# esquema-eletrico-17103449.net
KiCad netlist of a schematic drawn in EAGLE
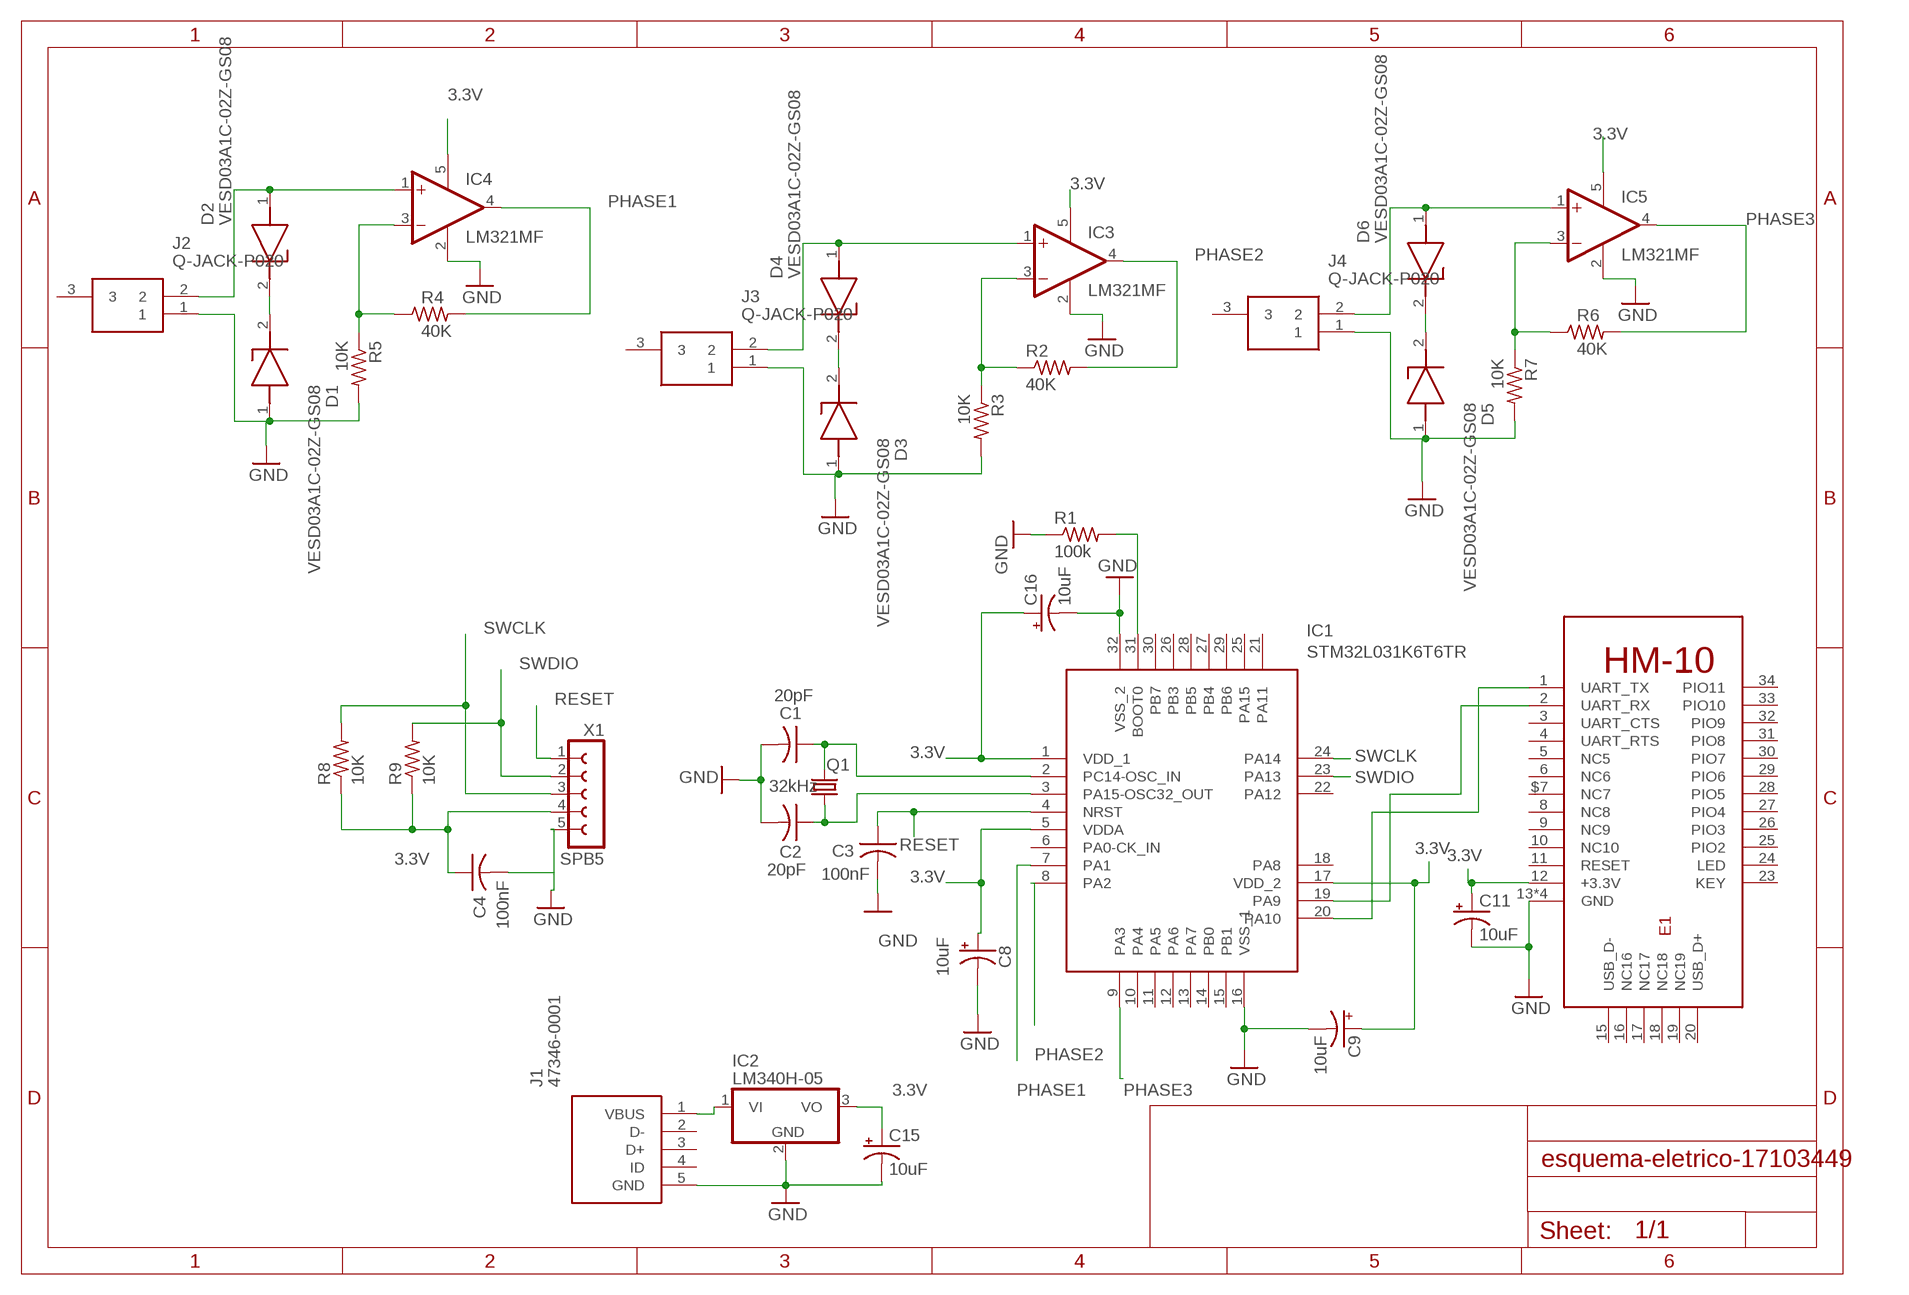
[diagram p0: schematic, sheet 1]

(export (version "E")
  (design (tool "Eeschema 10.0.6"))
  (components
    (comp (ref "C1")
      (value "20pF")
      (footprint "eagle-import:C0805")
      (libsource (lib "eagle-import") (part "C-USC0805"))
    )
    (comp (ref "C2")
      (value "20pF")
      (footprint "eagle-import:C0805")
      (libsource (lib "eagle-import") (part "C-USC0805"))
    )
    (comp (ref "C3")
      (value "100nF")
      (footprint "eagle-import:C0805")
      (libsource (lib "eagle-import") (part "C-USC0805"))
    )
    (comp (ref "C4")
      (value "100nF")
      (footprint "eagle-import:C0805")
      (libsource (lib "eagle-import") (part "C-USC0805"))
    )
    (comp (ref "C8")
      (value "10uF")
      (footprint "eagle-import:E2-5")
      (libsource (lib "eagle-import") (part "CPOL-USE2-5"))
    )
    (comp (ref "C9")
      (value "10uF")
      (footprint "eagle-import:E2-5")
      (libsource (lib "eagle-import") (part "CPOL-USE2-5"))
    )
    (comp (ref "C11")
      (value "10uF")
      (footprint "eagle-import:E2-5")
      (libsource (lib "eagle-import") (part "CPOL-USE2-5"))
    )
    (comp (ref "C15")
      (value "10uF")
      (footprint "eagle-import:E2-5")
      (libsource (lib "eagle-import") (part "CPOL-USE2-5"))
    )
    (comp (ref "C16")
      (value "10uF")
      (footprint "eagle-import:E2-5")
      (libsource (lib "eagle-import") (part "CPOL-USE2-5"))
    )
    (comp (ref "D1")
      (value "VESD03A1C-02Z-GS08")
      (footprint "eagle-import:VESD03A1C02ZGS08")
      (fields (field (name "MOUSER_PART_NUMBER") "78-VESD03A1C-02Z"))
      (libsource (lib "eagle-import") (part "VESD03A1C-02Z-GS08"))
    )
    (comp (ref "D2")
      (value "VESD03A1C-02Z-GS08")
      (footprint "eagle-import:VESD03A1C02ZGS08")
      (fields (field (name "MOUSER_PART_NUMBER") "78-VESD03A1C-02Z"))
      (libsource (lib "eagle-import") (part "VESD03A1C-02Z-GS08"))
    )
    (comp (ref "D3")
      (value "VESD03A1C-02Z-GS08")
      (footprint "eagle-import:VESD03A1C02ZGS08")
      (fields (field (name "MOUSER_PART_NUMBER") "78-VESD03A1C-02Z"))
      (libsource (lib "eagle-import") (part "VESD03A1C-02Z-GS08"))
    )
    (comp (ref "D4")
      (value "VESD03A1C-02Z-GS08")
      (footprint "eagle-import:VESD03A1C02ZGS08")
      (fields (field (name "MOUSER_PART_NUMBER") "78-VESD03A1C-02Z"))
      (libsource (lib "eagle-import") (part "VESD03A1C-02Z-GS08"))
    )
    (comp (ref "D5")
      (value "VESD03A1C-02Z-GS08")
      (footprint "eagle-import:VESD03A1C02ZGS08")
      (fields (field (name "MOUSER_PART_NUMBER") "78-VESD03A1C-02Z"))
      (libsource (lib "eagle-import") (part "VESD03A1C-02Z-GS08"))
    )
    (comp (ref "D6")
      (value "VESD03A1C-02Z-GS08")
      (footprint "eagle-import:VESD03A1C02ZGS08")
      (fields (field (name "MOUSER_PART_NUMBER") "78-VESD03A1C-02Z"))
      (libsource (lib "eagle-import") (part "VESD03A1C-02Z-GS08"))
    )
    (comp (ref "E1")
      (value "HM-10-BOARD")
      (footprint "eagle-import:26.9X13X2.2_BOARD")
      (libsource (lib "eagle-import") (part "HM-10-BOARD"))
    )
    (comp (ref "IC1")
      (value "STM32L031K6T6TR")
      (footprint "eagle-import:QFP80P900X900X160-32N")
      (fields (field (name "MOUSER_PART_NUMBER") "511-STM32L031K6T6TR"))
      (libsource (lib "eagle-import") (part "STM32L031K6T6TR"))
    )
    (comp (ref "IC2")
      (value "LM340H-05")
      (footprint "eagle-import:TO220H")
      (libsource (lib "eagle-import") (part "LM340?-H05"))
    )
    (comp (ref "IC3")
      (value "LM321MF")
      (footprint "eagle-import:SOT23-5")
      (libsource (lib "eagle-import") (part "LM321?MF"))
    )
    (comp (ref "IC4")
      (value "LM321MF")
      (footprint "eagle-import:SOT23-5")
      (libsource (lib "eagle-import") (part "LM321?MF"))
    )
    (comp (ref "IC5")
      (value "LM321MF")
      (footprint "eagle-import:SOT23-5")
      (libsource (lib "eagle-import") (part "LM321?MF"))
    )
    (comp (ref "J1")
      (value "47346-0001")
      (footprint "eagle-import:47346-0001")
      (fields (field (name "MOUSER_PART_NUMBER") "538-47346-0001"))
      (libsource (lib "eagle-import") (part "47346-0001"))
    )
    (comp (ref "J2")
      (value "Q-JACK-P020")
      (footprint "eagle-import:QJACKP020")
      (libsource (lib "eagle-import") (part "Q-JACK-P020"))
    )
    (comp (ref "J3")
      (value "Q-JACK-P020")
      (footprint "eagle-import:QJACKP020")
      (libsource (lib "eagle-import") (part "Q-JACK-P020"))
    )
    (comp (ref "J4")
      (value "Q-JACK-P020")
      (footprint "eagle-import:QJACKP020")
      (libsource (lib "eagle-import") (part "Q-JACK-P020"))
    )
    (comp (ref "Q1")
      (value "32kHz")
      (footprint "eagle-import:HC49_S")
      (libsource (lib "eagle-import") (part "CRYSTALHC49S"))
    )
    (comp (ref "R1")
      (value "100k")
      (footprint "eagle-import:0204_7")
      (libsource (lib "eagle-import") (part "R-US_0204/7"))
    )
    (comp (ref "R2")
      (value "40K")
      (footprint "eagle-import:WSC2515")
      (libsource (lib "eagle-import") (part "R-US_WSC2515"))
    )
    (comp (ref "R3")
      (value "10K")
      (footprint "eagle-import:WSC2515")
      (libsource (lib "eagle-import") (part "R-US_WSC2515"))
    )
    (comp (ref "R4")
      (value "40K")
      (footprint "eagle-import:WSC2515")
      (libsource (lib "eagle-import") (part "R-US_WSC2515"))
    )
    (comp (ref "R5")
      (value "10K")
      (footprint "eagle-import:WSC2515")
      (libsource (lib "eagle-import") (part "R-US_WSC2515"))
    )
    (comp (ref "R6")
      (value "40K")
      (footprint "eagle-import:WSC2515")
      (libsource (lib "eagle-import") (part "R-US_WSC2515"))
    )
    (comp (ref "R7")
      (value "10K")
      (footprint "eagle-import:WSC2515")
      (libsource (lib "eagle-import") (part "R-US_WSC2515"))
    )
    (comp (ref "R8")
      (value "10K")
      (footprint "eagle-import:WSC2515")
      (libsource (lib "eagle-import") (part "R-US_WSC2515"))
    )
    (comp (ref "R9")
      (value "10K")
      (footprint "eagle-import:WSC2515")
      (libsource (lib "eagle-import") (part "R-US_WSC2515"))
    )
    (comp (ref "X1")
      (value "SPB5")
      (footprint "eagle-import:SPB5")
      (libsource (lib "eagle-import") (part "SPB5"))
    )
  )
  (nets
    (net (code "1") (name "/3.3V") (class "Default")
      (node (ref "C11") (pin "+") (pinfunction "+_+") (pintype "passive"))
      (node (ref "C15") (pin "+") (pinfunction "+_+") (pintype "passive"))
      (node (ref "C16") (pin "+") (pinfunction "+_+") (pintype "passive"))
      (node (ref "C4") (pin "1") (pinfunction "1_1") (pintype "passive"))
      (node (ref "C8") (pin "+") (pinfunction "+_+") (pintype "passive"))
      (node (ref "C9") (pin "+") (pinfunction "+_+") (pintype "passive"))
      (node (ref "E1") (pin "12") (pinfunction "+3.3V_12") (pintype "bidirectional"))
      (node (ref "IC1") (pin "1") (pinfunction "VDD_1_1") (pintype "bidirectional"))
      (node (ref "IC1") (pin "17") (pinfunction "VDD_2_17") (pintype "bidirectional"))
      (node (ref "IC1") (pin "5") (pinfunction "VDDA_5") (pintype "bidirectional"))
      (node (ref "IC2") (pin "3") (pinfunction "VO_3") (pintype "passive"))
      (node (ref "IC3") (pin "5") (pinfunction "V+_5") (pintype "power_in"))
      (node (ref "IC4") (pin "5") (pinfunction "V+_5") (pintype "power_in"))
      (node (ref "R8") (pin "1") (pinfunction "1_1") (pintype "passive"))
      (node (ref "R9") (pin "1") (pinfunction "1_1") (pintype "passive"))
      (node (ref "X1") (pin "4") (pinfunction "4_4") (pintype "passive"))
    )
    (net (code "2") (name "/PHASE1") (class "Default")
      (node (ref "IC1") (pin "7") (pinfunction "PA1_7") (pintype "bidirectional"))
      (node (ref "IC4") (pin "4") (pinfunction "OUT_4") (pintype "output"))
      (node (ref "R4") (pin "2") (pinfunction "2_2") (pintype "passive"))
    )
    (net (code "3") (name "/PHASE2") (class "Default")
      (node (ref "IC1") (pin "8") (pinfunction "PA2_8") (pintype "bidirectional"))
      (node (ref "IC3") (pin "4") (pinfunction "OUT_4") (pintype "output"))
      (node (ref "R2") (pin "2") (pinfunction "2_2") (pintype "passive"))
    )
    (net (code "4") (name "/PHASE3") (class "Default")
      (node (ref "IC1") (pin "9") (pinfunction "PA3_9") (pintype "bidirectional"))
      (node (ref "IC5") (pin "4") (pinfunction "OUT_4") (pintype "output"))
      (node (ref "R6") (pin "2") (pinfunction "2_2") (pintype "passive"))
    )
    (net (code "5") (name "/RESET") (class "Default")
      (node (ref "C3") (pin "1") (pinfunction "1_1") (pintype "passive"))
      (node (ref "IC1") (pin "4") (pinfunction "NRST_4") (pintype "bidirectional"))
      (node (ref "X1") (pin "1") (pinfunction "1_1") (pintype "passive"))
    )
    (net (code "6") (name "/SWCLK") (class "Default")
      (node (ref "IC1") (pin "24") (pinfunction "PA14_24") (pintype "bidirectional"))
      (node (ref "R8") (pin "2") (pinfunction "2_2") (pintype "passive"))
      (node (ref "X1") (pin "3") (pinfunction "3_3") (pintype "passive"))
    )
    (net (code "7") (name "/SWDIO") (class "Default")
      (node (ref "IC1") (pin "23") (pinfunction "PA13_23") (pintype "bidirectional"))
      (node (ref "R9") (pin "2") (pinfunction "2_2") (pintype "passive"))
      (node (ref "X1") (pin "2") (pinfunction "2_2") (pintype "passive"))
    )
    (net (code "8") (name "GND") (class "Default")
      (node (ref "C1") (pin "2") (pinfunction "2_2") (pintype "passive"))
      (node (ref "C11") (pin "-") (pinfunction "-_-") (pintype "passive"))
      (node (ref "C15") (pin "-") (pinfunction "-_-") (pintype "passive"))
      (node (ref "C16") (pin "-") (pinfunction "-_-") (pintype "passive"))
      (node (ref "C2") (pin "2") (pinfunction "2_2") (pintype "passive"))
      (node (ref "C3") (pin "2") (pinfunction "2_2") (pintype "passive"))
      (node (ref "C4") (pin "2") (pinfunction "2_2") (pintype "passive"))
      (node (ref "C8") (pin "-") (pinfunction "-_-") (pintype "passive"))
      (node (ref "C9") (pin "-") (pinfunction "-_-") (pintype "passive"))
      (node (ref "D1") (pin "1") (pinfunction "A_1") (pintype "bidirectional"))
      (node (ref "D3") (pin "1") (pinfunction "A_1") (pintype "bidirectional"))
      (node (ref "D5") (pin "1") (pinfunction "A_1") (pintype "bidirectional"))
      (node (ref "E1") (pin "13") (pinfunction "GND_13") (pintype "bidirectional"))
      (node (ref "E1") (pin "14") (pinfunction "GND_14") (pintype "bidirectional"))
      (node (ref "E1") (pin "21") (pinfunction "GND_21") (pintype "bidirectional"))
      (node (ref "E1") (pin "22") (pinfunction "GND_22") (pintype "bidirectional"))
      (node (ref "IC1") (pin "16") (pinfunction "VSS_1_16") (pintype "bidirectional"))
      (node (ref "IC1") (pin "32") (pinfunction "VSS_2_32") (pintype "bidirectional"))
      (node (ref "IC2") (pin "2") (pinfunction "GND_2") (pintype "passive"))
      (node (ref "IC3") (pin "2") (pinfunction "V-_2") (pintype "power_in"))
      (node (ref "IC4") (pin "2") (pinfunction "V-_2") (pintype "power_in"))
      (node (ref "IC5") (pin "2") (pinfunction "V-_2") (pintype "power_in"))
      (node (ref "J1") (pin "5") (pinfunction "GND_5") (pintype "bidirectional"))
      (node (ref "J2") (pin "1") (pinfunction "1_1") (pintype "bidirectional"))
      (node (ref "J3") (pin "1") (pinfunction "1_1") (pintype "bidirectional"))
      (node (ref "J4") (pin "1") (pinfunction "1_1") (pintype "bidirectional"))
      (node (ref "R1") (pin "1") (pinfunction "1_1") (pintype "passive"))
      (node (ref "R3") (pin "2") (pinfunction "2_2") (pintype "passive"))
      (node (ref "R5") (pin "2") (pinfunction "2_2") (pintype "passive"))
      (node (ref "R7") (pin "2") (pinfunction "2_2") (pintype "passive"))
      (node (ref "X1") (pin "5") (pinfunction "5_5") (pintype "passive"))
    )
    (net (code "9") (name "Net-(D1-K)") (class "Default")
      (node (ref "D1") (pin "2") (pinfunction "K_2") (pintype "bidirectional"))
      (node (ref "D2") (pin "2") (pinfunction "K_2") (pintype "bidirectional"))
    )
    (net (code "10") (name "Net-(D2-A)") (class "Default")
      (node (ref "D2") (pin "1") (pinfunction "A_1") (pintype "bidirectional"))
      (node (ref "IC4") (pin "1") (pinfunction "+IN_1") (pintype "input"))
      (node (ref "J2") (pin "2") (pinfunction "2_2") (pintype "bidirectional"))
    )
    (net (code "11") (name "Net-(D3-K)") (class "Default")
      (node (ref "D3") (pin "2") (pinfunction "K_2") (pintype "bidirectional"))
      (node (ref "D4") (pin "2") (pinfunction "K_2") (pintype "bidirectional"))
    )
    (net (code "12") (name "Net-(D4-A)") (class "Default")
      (node (ref "D4") (pin "1") (pinfunction "A_1") (pintype "bidirectional"))
      (node (ref "IC3") (pin "1") (pinfunction "+IN_1") (pintype "input"))
      (node (ref "J3") (pin "2") (pinfunction "2_2") (pintype "bidirectional"))
    )
    (net (code "13") (name "Net-(D5-K)") (class "Default")
      (node (ref "D5") (pin "2") (pinfunction "K_2") (pintype "bidirectional"))
      (node (ref "D6") (pin "2") (pinfunction "K_2") (pintype "bidirectional"))
    )
    (net (code "14") (name "Net-(D6-A)") (class "Default")
      (node (ref "D6") (pin "1") (pinfunction "A_1") (pintype "bidirectional"))
      (node (ref "IC5") (pin "1") (pinfunction "+IN_1") (pintype "input"))
      (node (ref "J4") (pin "2") (pinfunction "2_2") (pintype "bidirectional"))
    )
    (net (code "15") (name "Net-(E1-UART_RX)") (class "Default")
      (node (ref "E1") (pin "2") (pinfunction "UART_RX_2") (pintype "bidirectional"))
      (node (ref "IC1") (pin "19") (pinfunction "PA9_19") (pintype "bidirectional"))
    )
    (net (code "16") (name "Net-(E1-UART_TX)") (class "Default")
      (node (ref "E1") (pin "1") (pinfunction "UART_TX_1") (pintype "bidirectional"))
      (node (ref "IC1") (pin "20") (pinfunction "PA10_20") (pintype "bidirectional"))
    )
    (net (code "17") (name "Net-(IC1-BOOT0)") (class "Default")
      (node (ref "IC1") (pin "31") (pinfunction "BOOT0_31") (pintype "bidirectional"))
      (node (ref "R1") (pin "2") (pinfunction "2_2") (pintype "passive"))
    )
    (net (code "18") (name "Net-(IC1-PA15-OSC32_OUT)") (class "Default")
      (node (ref "C2") (pin "1") (pinfunction "1_1") (pintype "passive"))
      (node (ref "IC1") (pin "3") (pinfunction "PA15-OSC32_OUT_3") (pintype "bidirectional"))
      (node (ref "Q1") (pin "1") (pinfunction "1_1") (pintype "passive"))
    )
    (net (code "19") (name "Net-(IC1-PC14-OSC_IN)") (class "Default")
      (node (ref "C1") (pin "1") (pinfunction "1_1") (pintype "passive"))
      (node (ref "IC1") (pin "2") (pinfunction "PC14-OSC_IN_2") (pintype "bidirectional"))
      (node (ref "Q1") (pin "2") (pinfunction "2_2") (pintype "passive"))
    )
    (net (code "20") (name "Net-(IC2-VI)") (class "Default")
      (node (ref "IC2") (pin "1") (pinfunction "VI_1") (pintype "input"))
      (node (ref "J1") (pin "1") (pinfunction "VBUS_1") (pintype "bidirectional"))
    )
    (net (code "21") (name "Net-(IC3--IN)") (class "Default")
      (node (ref "IC3") (pin "3") (pinfunction "-IN_3") (pintype "input"))
      (node (ref "R2") (pin "1") (pinfunction "1_1") (pintype "passive"))
      (node (ref "R3") (pin "1") (pinfunction "1_1") (pintype "passive"))
    )
    (net (code "22") (name "Net-(IC4--IN)") (class "Default")
      (node (ref "IC4") (pin "3") (pinfunction "-IN_3") (pintype "input"))
      (node (ref "R4") (pin "1") (pinfunction "1_1") (pintype "passive"))
      (node (ref "R5") (pin "1") (pinfunction "1_1") (pintype "passive"))
    )
    (net (code "23") (name "Net-(IC5--IN)") (class "Default")
      (node (ref "IC5") (pin "3") (pinfunction "-IN_3") (pintype "input"))
      (node (ref "R6") (pin "1") (pinfunction "1_1") (pintype "passive"))
      (node (ref "R7") (pin "1") (pinfunction "1_1") (pintype "passive"))
    )
    (net (code "24") (name "unconnected-(E1-KEY-Pad23)") (class "Default")
      (node (ref "E1") (pin "23") (pinfunction "KEY_23") (pintype "bidirectional"))
    )
    (net (code "25") (name "unconnected-(E1-LED-Pad24)") (class "Default")
      (node (ref "E1") (pin "24") (pinfunction "LED_24") (pintype "bidirectional"))
    )
    (net (code "26") (name "unconnected-(E1-NC5-Pad5)") (class "Default")
      (node (ref "E1") (pin "5") (pinfunction "NC5_5") (pintype "bidirectional"))
    )
    (net (code "27") (name "unconnected-(E1-NC6-Pad6)") (class "Default")
      (node (ref "E1") (pin "6") (pinfunction "NC6_6") (pintype "bidirectional"))
    )
    (net (code "28") (name "unconnected-(E1-NC7-Pad$7)") (class "Default")
      (node (ref "E1") (pin "$7") (pinfunction "NC7_$7") (pintype "bidirectional"))
    )
    (net (code "29") (name "unconnected-(E1-NC8-Pad8)") (class "Default")
      (node (ref "E1") (pin "8") (pinfunction "NC8_8") (pintype "bidirectional"))
    )
    (net (code "30") (name "unconnected-(E1-NC9-Pad9)") (class "Default")
      (node (ref "E1") (pin "9") (pinfunction "NC9_9") (pintype "bidirectional"))
    )
    (net (code "31") (name "unconnected-(E1-NC10-Pad10)") (class "Default")
      (node (ref "E1") (pin "10") (pinfunction "NC10_10") (pintype "bidirectional"))
    )
    (net (code "32") (name "unconnected-(E1-NC16-Pad16)") (class "Default")
      (node (ref "E1") (pin "16") (pinfunction "NC16_16") (pintype "bidirectional"))
    )
    (net (code "33") (name "unconnected-(E1-NC17-Pad17)") (class "Default")
      (node (ref "E1") (pin "17") (pinfunction "NC17_17") (pintype "bidirectional"))
    )
    (net (code "34") (name "unconnected-(E1-NC18-Pad18)") (class "Default")
      (node (ref "E1") (pin "18") (pinfunction "NC18_18") (pintype "bidirectional"))
    )
    (net (code "35") (name "unconnected-(E1-NC19-Pad19)") (class "Default")
      (node (ref "E1") (pin "19") (pinfunction "NC19_19") (pintype "bidirectional"))
    )
    (net (code "36") (name "unconnected-(E1-PIO2-Pad25)") (class "Default")
      (node (ref "E1") (pin "25") (pinfunction "PIO2_25") (pintype "bidirectional"))
    )
    (net (code "37") (name "unconnected-(E1-PIO3-Pad26)") (class "Default")
      (node (ref "E1") (pin "26") (pinfunction "PIO3_26") (pintype "bidirectional"))
    )
    (net (code "38") (name "unconnected-(E1-PIO4-Pad27)") (class "Default")
      (node (ref "E1") (pin "27") (pinfunction "PIO4_27") (pintype "bidirectional"))
    )
    (net (code "39") (name "unconnected-(E1-PIO5-Pad28)") (class "Default")
      (node (ref "E1") (pin "28") (pinfunction "PIO5_28") (pintype "bidirectional"))
    )
    (net (code "40") (name "unconnected-(E1-PIO6-Pad29)") (class "Default")
      (node (ref "E1") (pin "29") (pinfunction "PIO6_29") (pintype "bidirectional"))
    )
    (net (code "41") (name "unconnected-(E1-PIO7-Pad30)") (class "Default")
      (node (ref "E1") (pin "30") (pinfunction "PIO7_30") (pintype "bidirectional"))
    )
    (net (code "42") (name "unconnected-(E1-PIO8-Pad31)") (class "Default")
      (node (ref "E1") (pin "31") (pinfunction "PIO8_31") (pintype "bidirectional"))
    )
    (net (code "43") (name "unconnected-(E1-PIO9-Pad32)") (class "Default")
      (node (ref "E1") (pin "32") (pinfunction "PIO9_32") (pintype "bidirectional"))
    )
    (net (code "44") (name "unconnected-(E1-PIO10-Pad33)") (class "Default")
      (node (ref "E1") (pin "33") (pinfunction "PIO10_33") (pintype "bidirectional"))
    )
    (net (code "45") (name "unconnected-(E1-PIO11-Pad34)") (class "Default")
      (node (ref "E1") (pin "34") (pinfunction "PIO11_34") (pintype "bidirectional"))
    )
    (net (code "46") (name "unconnected-(E1-RESET-Pad11)") (class "Default")
      (node (ref "E1") (pin "11") (pinfunction "RESET_11") (pintype "bidirectional"))
    )
    (net (code "47") (name "unconnected-(E1-UART_CTS-Pad3)") (class "Default")
      (node (ref "E1") (pin "3") (pinfunction "UART_CTS_3") (pintype "bidirectional"))
    )
    (net (code "48") (name "unconnected-(E1-UART_RTS-Pad4)") (class "Default")
      (node (ref "E1") (pin "4") (pinfunction "UART_RTS_4") (pintype "bidirectional"))
    )
    (net (code "49") (name "unconnected-(E1-USB_D+-Pad20)") (class "Default")
      (node (ref "E1") (pin "20") (pinfunction "USB_D+_20") (pintype "bidirectional"))
    )
    (net (code "50") (name "unconnected-(E1-USB_D--Pad15)") (class "Default")
      (node (ref "E1") (pin "15") (pinfunction "USB_D-_15") (pintype "bidirectional"))
    )
    (net (code "51") (name "unconnected-(IC1-PA0-CK_IN-Pad6)") (class "Default")
      (node (ref "IC1") (pin "6") (pinfunction "PA0-CK_IN_6") (pintype "bidirectional"))
    )
    (net (code "52") (name "unconnected-(IC1-PA4-Pad10)") (class "Default")
      (node (ref "IC1") (pin "10") (pinfunction "PA4_10") (pintype "bidirectional"))
    )
    (net (code "53") (name "unconnected-(IC1-PA5-Pad11)") (class "Default")
      (node (ref "IC1") (pin "11") (pinfunction "PA5_11") (pintype "bidirectional"))
    )
    (net (code "54") (name "unconnected-(IC1-PA6-Pad12)") (class "Default")
      (node (ref "IC1") (pin "12") (pinfunction "PA6_12") (pintype "bidirectional"))
    )
    (net (code "55") (name "unconnected-(IC1-PA7-Pad13)") (class "Default")
      (node (ref "IC1") (pin "13") (pinfunction "PA7_13") (pintype "bidirectional"))
    )
    (net (code "56") (name "unconnected-(IC1-PA8-Pad18)") (class "Default")
      (node (ref "IC1") (pin "18") (pinfunction "PA8_18") (pintype "bidirectional"))
    )
    (net (code "57") (name "unconnected-(IC1-PA11-Pad21)") (class "Default")
      (node (ref "IC1") (pin "21") (pinfunction "PA11_21") (pintype "bidirectional"))
    )
    (net (code "58") (name "unconnected-(IC1-PA12-Pad22)") (class "Default")
      (node (ref "IC1") (pin "22") (pinfunction "PA12_22") (pintype "bidirectional"))
    )
    (net (code "59") (name "unconnected-(IC1-PA15-Pad25)") (class "Default")
      (node (ref "IC1") (pin "25") (pinfunction "PA15_25") (pintype "bidirectional"))
    )
    (net (code "60") (name "unconnected-(IC1-PB0-Pad14)") (class "Default")
      (node (ref "IC1") (pin "14") (pinfunction "PB0_14") (pintype "bidirectional"))
    )
    (net (code "61") (name "unconnected-(IC1-PB1-Pad15)") (class "Default")
      (node (ref "IC1") (pin "15") (pinfunction "PB1_15") (pintype "bidirectional"))
    )
    (net (code "62") (name "unconnected-(IC1-PB3-Pad26)") (class "Default")
      (node (ref "IC1") (pin "26") (pinfunction "PB3_26") (pintype "bidirectional"))
    )
    (net (code "63") (name "unconnected-(IC1-PB4-Pad27)") (class "Default")
      (node (ref "IC1") (pin "27") (pinfunction "PB4_27") (pintype "bidirectional"))
    )
    (net (code "64") (name "unconnected-(IC1-PB5-Pad28)") (class "Default")
      (node (ref "IC1") (pin "28") (pinfunction "PB5_28") (pintype "bidirectional"))
    )
    (net (code "65") (name "unconnected-(IC1-PB6-Pad29)") (class "Default")
      (node (ref "IC1") (pin "29") (pinfunction "PB6_29") (pintype "bidirectional"))
    )
    (net (code "66") (name "unconnected-(IC1-PB7-Pad30)") (class "Default")
      (node (ref "IC1") (pin "30") (pinfunction "PB7_30") (pintype "bidirectional"))
    )
    (net (code "67") (name "unconnected-(IC5-V+-Pad5)") (class "Default")
      (node (ref "IC5") (pin "5") (pinfunction "V+_5") (pintype "power_in"))
    )
    (net (code "68") (name "unconnected-(J1-D+-Pad3)") (class "Default")
      (node (ref "J1") (pin "3") (pinfunction "D+_3") (pintype "bidirectional"))
    )
    (net (code "69") (name "unconnected-(J1-D--Pad2)") (class "Default")
      (node (ref "J1") (pin "2") (pinfunction "D-_2") (pintype "bidirectional"))
    )
    (net (code "70") (name "unconnected-(J1-ID-Pad4)") (class "Default")
      (node (ref "J1") (pin "4") (pinfunction "ID_4") (pintype "bidirectional"))
    )
    (net (code "71") (name "unconnected-(J2-Pad3)") (class "Default")
      (node (ref "J2") (pin "3") (pinfunction "3_3") (pintype "bidirectional"))
    )
    (net (code "72") (name "unconnected-(J3-Pad3)") (class "Default")
      (node (ref "J3") (pin "3") (pinfunction "3_3") (pintype "bidirectional"))
    )
    (net (code "73") (name "unconnected-(J4-Pad3)") (class "Default")
      (node (ref "J4") (pin "3") (pinfunction "3_3") (pintype "bidirectional"))
    )
  )
)
